# Connectors_PIN_Header.net
KiCad netlist of a schematic drawn in Altium Designer
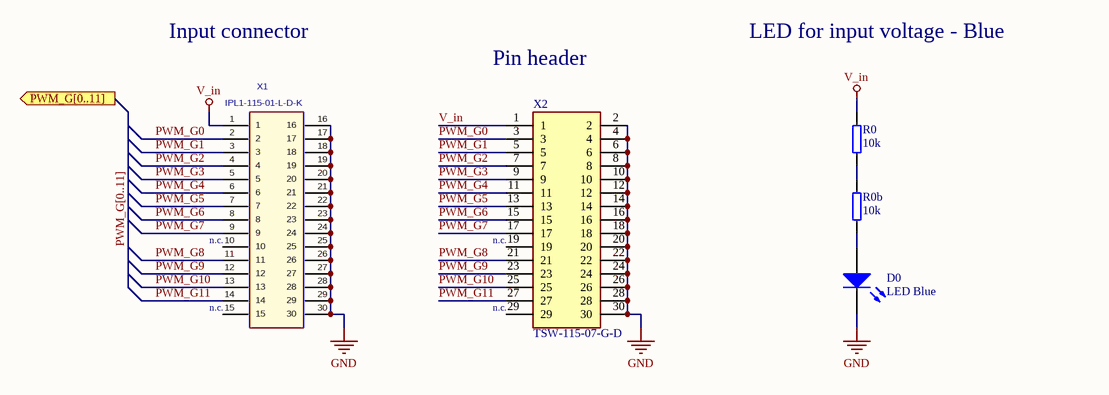
[diagram p0: Connectors&PIN_Header.SchDoc]

(export (version "E")
  (design (tool "Eeschema 10.0.6"))
  (components
    (comp (ref "D0")
      (value "LED Blue")
      (footprint "WL-SMCW_0603")
      (description "Standard LEDs - SMD 0603 blue")
      (fields
        (field (name "MANUFACTURER PART NUMBER") "UZgen_LED_0603_Blue")
        (field (name "MANUFACTURER") "UZgen")
        (field (name "CREATED FROM") "UZgenTool")
      )
      (libsource (lib "user") (part "LED_Blue"))
    )
    (comp (ref "R0")
      (value "10k")
      (footprint "RES 0603_1608")
      (description "SMD resistor 0.1%, 10ppm")
      (fields
        (field (name "MANUFACTURER PART NUMBER") "RQ73C1J10KBTD")
        (field (name "MANUFACTURER") "TE Connectivity")
        (field (name "CREATED FROM") "DHufnagel")
      )
      (libsource (lib "user") (part "Resistor"))
    )
    (comp (ref "R0b")
      (value "10k")
      (footprint "RES 0603_1608")
      (description "SMD resistor 0.1%, 10ppm")
      (fields
        (field (name "MANUFACTURER PART NUMBER") "RQ73C1J10KBTD")
        (field (name "MANUFACTURER") "TE Connectivity")
        (field (name "CREATED FROM") "DHufnagel")
      )
      (libsource (lib "user") (part "Resistor"))
    )
    (comp (ref "X1")
      (value "IPL1-115-01-L-D-K")
      (footprint "IPL1-115-01-YYY-D-K")
      (description "2.54 mm Double Row Terminal Assembly")
      (fields
        (field (name "MANUFACTURER") "SAMTEC")
        (field (name "LCSC PART NUMBER") "C17431809")
        (field (name "CREATED FROM") "MGremer")
      )
      (libsource (lib "user") (part "IPL1-115-01-XX-D-XX"))
    )
    (comp (ref "X2")
      (value "TSW-115-07-G-D")
      (footprint "TSW-115-XX-YY-D")
      (description "2x15 Pins")
      (fields
        (field (name "MOUSER PART NUMBER") "200-TSW11507GD")
        (field (name "MANUFACTURER") "SAMTEC")
        (field (name "CREATED FROM") "JHahn")
      )
      (libsource (lib "user") (part "TSW-115-07-G-D"))
    )
  )
  (nets
    (net (code "1") (name "/PWM_G0") (class "Default")
      (node (ref "X1") (pin "2") (pinfunction "2_2") (pintype "passive"))
      (node (ref "X2") (pin "3") (pinfunction "3_3") (pintype "passive"))
    )
    (net (code "2") (name "/PWM_G1") (class "Default")
      (node (ref "X1") (pin "3") (pinfunction "3_3") (pintype "passive"))
      (node (ref "X2") (pin "5") (pinfunction "5_5") (pintype "passive"))
    )
    (net (code "3") (name "/PWM_G2") (class "Default")
      (node (ref "X1") (pin "4") (pinfunction "4_4") (pintype "passive"))
      (node (ref "X2") (pin "7") (pinfunction "7_7") (pintype "passive"))
    )
    (net (code "4") (name "/PWM_G3") (class "Default")
      (node (ref "X1") (pin "5") (pinfunction "5_5") (pintype "passive"))
      (node (ref "X2") (pin "9") (pinfunction "9_9") (pintype "passive"))
    )
    (net (code "5") (name "/PWM_G4") (class "Default")
      (node (ref "X1") (pin "6") (pinfunction "6_6") (pintype "passive"))
      (node (ref "X2") (pin "11") (pinfunction "11_11") (pintype "passive"))
    )
    (net (code "6") (name "/PWM_G5") (class "Default")
      (node (ref "X1") (pin "7") (pinfunction "7_7") (pintype "passive"))
      (node (ref "X2") (pin "13") (pinfunction "13_13") (pintype "passive"))
    )
    (net (code "7") (name "/PWM_G6") (class "Default")
      (node (ref "X1") (pin "8") (pinfunction "8_8") (pintype "passive"))
      (node (ref "X2") (pin "15") (pinfunction "15_15") (pintype "passive"))
    )
    (net (code "8") (name "/PWM_G7") (class "Default")
      (node (ref "X1") (pin "9") (pinfunction "9_9") (pintype "passive"))
      (node (ref "X2") (pin "17") (pinfunction "17_17") (pintype "passive"))
    )
    (net (code "9") (name "/PWM_G8") (class "Default")
      (node (ref "X1") (pin "11") (pinfunction "11_11") (pintype "passive"))
      (node (ref "X2") (pin "21") (pinfunction "21_21") (pintype "passive"))
    )
    (net (code "10") (name "/PWM_G9") (class "Default")
      (node (ref "X1") (pin "12") (pinfunction "12_12") (pintype "passive"))
      (node (ref "X2") (pin "23") (pinfunction "23_23") (pintype "passive"))
    )
    (net (code "11") (name "/PWM_G10") (class "Default")
      (node (ref "X1") (pin "13") (pinfunction "13_13") (pintype "passive"))
      (node (ref "X2") (pin "25") (pinfunction "25_25") (pintype "passive"))
    )
    (net (code "12") (name "/PWM_G11") (class "Default")
      (node (ref "X1") (pin "14") (pinfunction "14_14") (pintype "passive"))
      (node (ref "X2") (pin "27") (pinfunction "27_27") (pintype "passive"))
    )
    (net (code "14") (name "GND") (class "Default")
      (node (ref "D0") (pin "1") (pinfunction "K_1") (pintype "passive"))
      (node (ref "X1") (pin "16") (pinfunction "16_16") (pintype "passive"))
      (node (ref "X1") (pin "17") (pinfunction "17_17") (pintype "passive"))
      (node (ref "X1") (pin "18") (pinfunction "18_18") (pintype "passive"))
      (node (ref "X1") (pin "19") (pinfunction "19_19") (pintype "passive"))
      (node (ref "X1") (pin "20") (pinfunction "20_20") (pintype "passive"))
      (node (ref "X1") (pin "21") (pinfunction "21_21") (pintype "passive"))
      (node (ref "X1") (pin "22") (pinfunction "22_22") (pintype "passive"))
      (node (ref "X1") (pin "23") (pinfunction "23_23") (pintype "passive"))
      (node (ref "X1") (pin "24") (pinfunction "24_24") (pintype "passive"))
      (node (ref "X1") (pin "25") (pinfunction "25_25") (pintype "passive"))
      (node (ref "X1") (pin "26") (pinfunction "26_26") (pintype "passive"))
      (node (ref "X1") (pin "27") (pinfunction "27_27") (pintype "passive"))
      (node (ref "X1") (pin "28") (pinfunction "28_28") (pintype "passive"))
      (node (ref "X1") (pin "29") (pinfunction "29_29") (pintype "passive"))
      (node (ref "X1") (pin "30") (pinfunction "30_30") (pintype "passive"))
      (node (ref "X2") (pin "10") (pinfunction "10_10") (pintype "passive"))
      (node (ref "X2") (pin "12") (pinfunction "12_12") (pintype "passive"))
      (node (ref "X2") (pin "14") (pinfunction "14_14") (pintype "passive"))
      (node (ref "X2") (pin "16") (pinfunction "16_16") (pintype "passive"))
      (node (ref "X2") (pin "18") (pinfunction "18_18") (pintype "passive"))
      (node (ref "X2") (pin "2") (pinfunction "2_2") (pintype "passive"))
      (node (ref "X2") (pin "20") (pinfunction "20_20") (pintype "passive"))
      (node (ref "X2") (pin "22") (pinfunction "22_22") (pintype "passive"))
      (node (ref "X2") (pin "24") (pinfunction "24_24") (pintype "passive"))
      (node (ref "X2") (pin "26") (pinfunction "26_26") (pintype "passive"))
      (node (ref "X2") (pin "28") (pinfunction "28_28") (pintype "passive"))
      (node (ref "X2") (pin "30") (pinfunction "30_30") (pintype "passive"))
      (node (ref "X2") (pin "4") (pinfunction "4_4") (pintype "passive"))
      (node (ref "X2") (pin "6") (pinfunction "6_6") (pintype "passive"))
      (node (ref "X2") (pin "8") (pinfunction "8_8") (pintype "passive"))
    )
    (net (code "15") (name "Net-(D0-A)") (class "Default")
      (node (ref "D0") (pin "2") (pinfunction "A_2") (pintype "passive"))
      (node (ref "R0b") (pin "1") (pinfunction "1_1") (pintype "passive"))
    )
    (net (code "16") (name "Net-(R0-Pad1)") (class "Default")
      (node (ref "R0") (pin "1") (pinfunction "1_1") (pintype "passive"))
      (node (ref "R0b") (pin "2") (pinfunction "2_2") (pintype "passive"))
    )
    (net (code "17") (name "V_in") (class "Default")
      (node (ref "R0") (pin "2") (pinfunction "2_2") (pintype "passive"))
      (node (ref "X1") (pin "1") (pinfunction "1_1") (pintype "passive"))
      (node (ref "X2") (pin "1") (pinfunction "1_1") (pintype "passive"))
    )
    (net (code "18") (name "unconnected-(X1-Pad10)") (class "Default")
      (node (ref "X1") (pin "10") (pinfunction "10_10") (pintype "passive"))
    )
    (net (code "19") (name "unconnected-(X1-Pad15)") (class "Default")
      (node (ref "X1") (pin "15") (pinfunction "15_15") (pintype "passive"))
    )
    (net (code "20") (name "unconnected-(X2-Pad19)") (class "Default")
      (node (ref "X2") (pin "19") (pinfunction "19_19") (pintype "passive"))
    )
    (net (code "21") (name "unconnected-(X2-Pad29)") (class "Default")
      (node (ref "X2") (pin "29") (pinfunction "29_29") (pintype "passive"))
    )
  )
)
